# receiver_1.net
KiCad netlist of a schematic drawn in Altium Designer
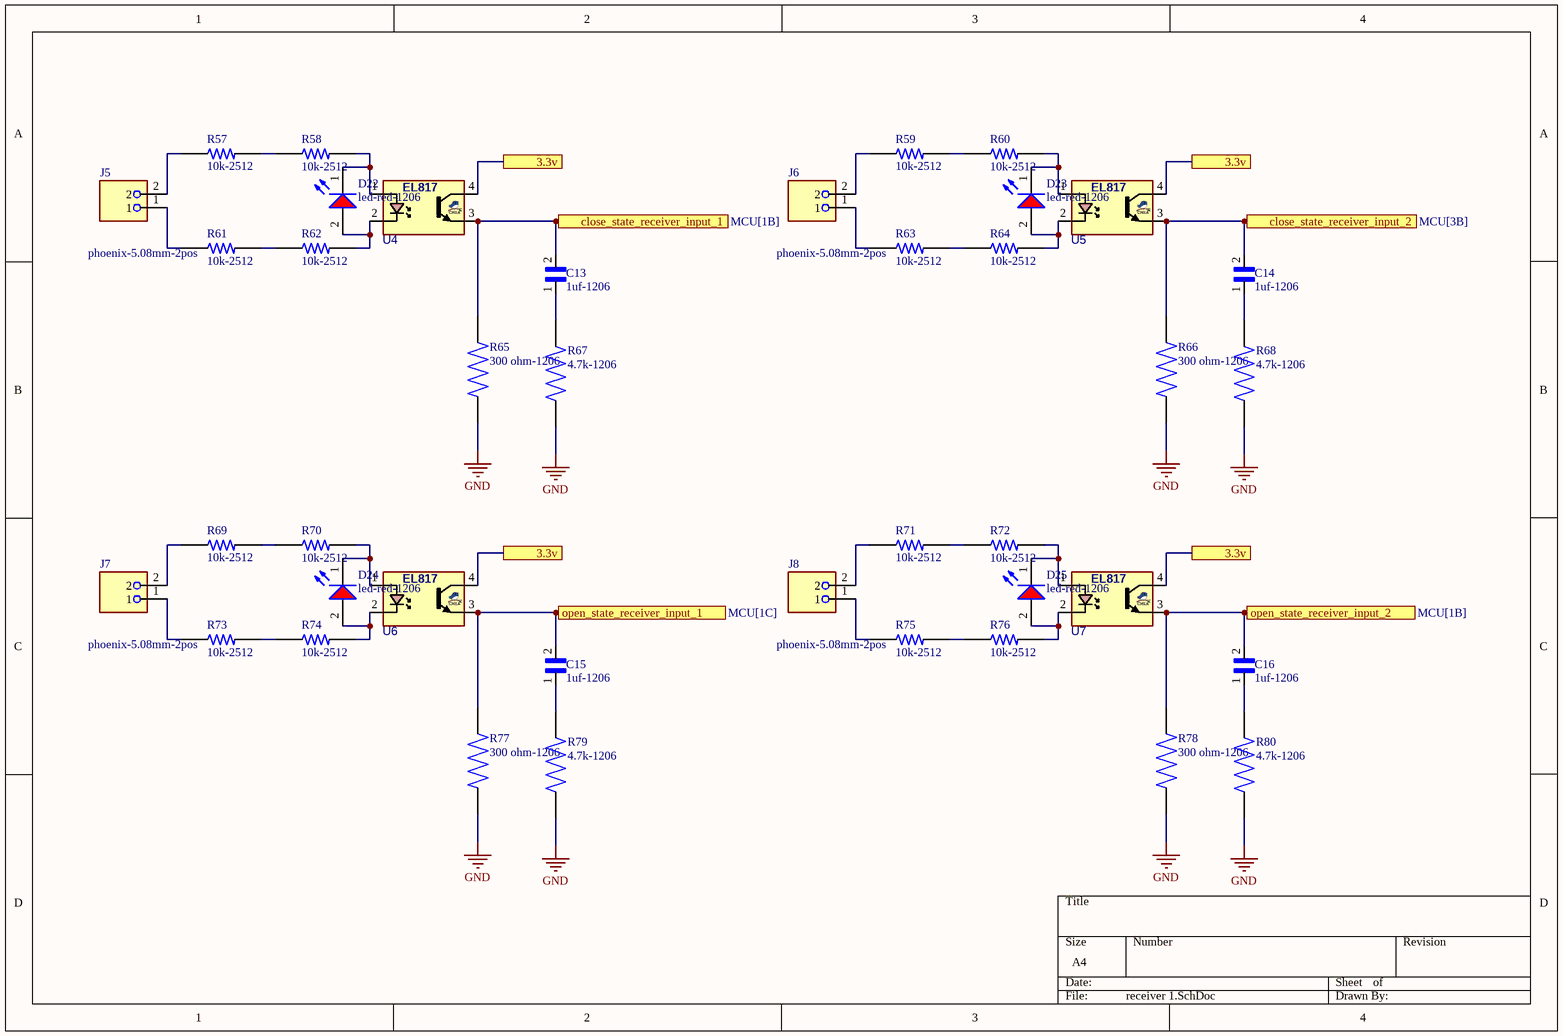
[diagram p0: receiver 1.SchDoc]

(export (version "E")
  (design (tool "Eeschema 10.0.6"))
  (components
    (comp (ref "C13")
      (value "1uf-1206")
      (footprint "CAPC3216X180N")
      (description "1ÂµF Â±20% 50V Ceramic Capacitor X8R 1206 (3216 Metric)")
      (fields (field (name "MF") "TDK") (field (name "MP") "CGA5L3X8R1H105M160AB"))
      (libsource (lib "cap-1206") (part "CGA5L3X8R1H105M160AB"))
    )
    (comp (ref "C14")
      (value "1uf-1206")
      (footprint "CAPC3216X180N")
      (description "1ÂµF Â±20% 50V Ceramic Capacitor X8R 1206 (3216 Metric)")
      (fields (field (name "MF") "TDK") (field (name "MP") "CGA5L3X8R1H105M160AB"))
      (libsource (lib "cap-1206") (part "CGA5L3X8R1H105M160AB"))
    )
    (comp (ref "C15")
      (value "1uf-1206")
      (footprint "CAPC3216X180N")
      (description "1ÂµF Â±20% 50V Ceramic Capacitor X8R 1206 (3216 Metric)")
      (fields (field (name "MF") "TDK") (field (name "MP") "CGA5L3X8R1H105M160AB"))
      (libsource (lib "cap-1206") (part "CGA5L3X8R1H105M160AB"))
    )
    (comp (ref "C16")
      (value "1uf-1206")
      (footprint "CAPC3216X180N")
      (description "1ÂµF Â±20% 50V Ceramic Capacitor X8R 1206 (3216 Metric)")
      (fields (field (name "MF") "TDK") (field (name "MP") "CGA5L3X8R1H105M160AB"))
      (libsource (lib "cap-1206") (part "CGA5L3X8R1H105M160AB"))
    )
    (comp (ref "D22")
      (value "led-red-1206")
      (footprint "WL-SMRW_1206 dome_normal use")
      (description "WL-SMRW Mono-color Reverse mount Waterclear, SMT, size 1206 dome, Red, 2V, 20°")
      (fields
        (field (name "MANUFACTURER PART NUMBER") "156120RS82500")
        (field (name "MANUFACTURER") "Wurth Elektronik")
      )
      (libsource (lib "led-1206") (part "156120RS82500"))
    )
    (comp (ref "D23")
      (value "led-red-1206")
      (footprint "WL-SMRW_1206 dome_normal use")
      (description "WL-SMRW Mono-color Reverse mount Waterclear, SMT, size 1206 dome, Red, 2V, 20°")
      (fields
        (field (name "MANUFACTURER PART NUMBER") "156120RS82500")
        (field (name "MANUFACTURER") "Wurth Elektronik")
      )
      (libsource (lib "led-1206") (part "156120RS82500"))
    )
    (comp (ref "D24")
      (value "led-red-1206")
      (footprint "WL-SMRW_1206 dome_normal use")
      (description "WL-SMRW Mono-color Reverse mount Waterclear, SMT, size 1206 dome, Red, 2V, 20°")
      (fields
        (field (name "MANUFACTURER PART NUMBER") "156120RS82500")
        (field (name "MANUFACTURER") "Wurth Elektronik")
      )
      (libsource (lib "led-1206") (part "156120RS82500"))
    )
    (comp (ref "D25")
      (value "led-red-1206")
      (footprint "WL-SMRW_1206 dome_normal use")
      (description "WL-SMRW Mono-color Reverse mount Waterclear, SMT, size 1206 dome, Red, 2V, 20°")
      (fields
        (field (name "MANUFACTURER PART NUMBER") "156120RS82500")
        (field (name "MANUFACTURER") "Wurth Elektronik")
      )
      (libsource (lib "led-1206") (part "156120RS82500"))
    )
    (comp (ref "J5")
      (value "phoenix-5.08mm-2pos")
      (footprint "PHOENIX_1715721")
      (fields (field (name "MP") "1715721"))
      (libsource (lib "phoenix-2pos") (part "1715721"))
    )
    (comp (ref "J6")
      (value "phoenix-5.08mm-2pos")
      (footprint "PHOENIX_1715721")
      (fields (field (name "MP") "1715721"))
      (libsource (lib "phoenix-2pos") (part "1715721"))
    )
    (comp (ref "J7")
      (value "phoenix-5.08mm-2pos")
      (footprint "PHOENIX_1715721")
      (fields (field (name "MP") "1715721"))
      (libsource (lib "phoenix-2pos") (part "1715721"))
    )
    (comp (ref "J8")
      (value "phoenix-5.08mm-2pos")
      (footprint "PHOENIX_1715721")
      (fields (field (name "MP") "1715721"))
      (libsource (lib "phoenix-2pos") (part "1715721"))
    )
    (comp (ref "R57")
      (value "10k-2512")
      (footprint "RESC6331X70N")
      (description "18 kOhms Â±5% 1.5W Chip Resistor 2512 (6432 Metric) Pulse Withstanding Thick Film")
      (fields (field (name "MF") "TE Connectivity") (field (name "MP") "5-2176246-2"))
      (libsource (lib "resistor-2512") (part "5-2176246-2"))
    )
    (comp (ref "R58")
      (value "10k-2512")
      (footprint "RESC6331X70N")
      (description "18 kOhms Â±5% 1.5W Chip Resistor 2512 (6432 Metric) Pulse Withstanding Thick Film")
      (fields (field (name "MF") "TE Connectivity") (field (name "MP") "5-2176246-2"))
      (libsource (lib "resistor-2512") (part "5-2176246-2"))
    )
    (comp (ref "R59")
      (value "10k-2512")
      (footprint "RESC6331X70N")
      (description "18 kOhms Â±5% 1.5W Chip Resistor 2512 (6432 Metric) Pulse Withstanding Thick Film")
      (fields (field (name "MF") "TE Connectivity") (field (name "MP") "5-2176246-2"))
      (libsource (lib "resistor-2512") (part "5-2176246-2"))
    )
    (comp (ref "R60")
      (value "10k-2512")
      (footprint "RESC6331X70N")
      (description "18 kOhms Â±5% 1.5W Chip Resistor 2512 (6432 Metric) Pulse Withstanding Thick Film")
      (fields (field (name "MF") "TE Connectivity") (field (name "MP") "5-2176246-2"))
      (libsource (lib "resistor-2512") (part "5-2176246-2"))
    )
    (comp (ref "R61")
      (value "10k-2512")
      (footprint "RESC6331X70N")
      (description "18 kOhms Â±5% 1.5W Chip Resistor 2512 (6432 Metric) Pulse Withstanding Thick Film")
      (fields (field (name "MF") "TE Connectivity") (field (name "MP") "5-2176246-2"))
      (libsource (lib "resistor-2512") (part "5-2176246-2"))
    )
    (comp (ref "R62")
      (value "10k-2512")
      (footprint "RESC6331X70N")
      (description "18 kOhms Â±5% 1.5W Chip Resistor 2512 (6432 Metric) Pulse Withstanding Thick Film")
      (fields (field (name "MF") "TE Connectivity") (field (name "MP") "5-2176246-2"))
      (libsource (lib "resistor-2512") (part "5-2176246-2"))
    )
    (comp (ref "R63")
      (value "10k-2512")
      (footprint "RESC6331X70N")
      (description "18 kOhms Â±5% 1.5W Chip Resistor 2512 (6432 Metric) Pulse Withstanding Thick Film")
      (fields (field (name "MF") "TE Connectivity") (field (name "MP") "5-2176246-2"))
      (libsource (lib "resistor-2512") (part "5-2176246-2"))
    )
    (comp (ref "R64")
      (value "10k-2512")
      (footprint "RESC6331X70N")
      (description "18 kOhms Â±5% 1.5W Chip Resistor 2512 (6432 Metric) Pulse Withstanding Thick Film")
      (fields (field (name "MF") "TE Connectivity") (field (name "MP") "5-2176246-2"))
      (libsource (lib "resistor-2512") (part "5-2176246-2"))
    )
    (comp (ref "R65")
      (value "300 ohm-1206")
      (footprint "RESC3015X65N")
      (description "Res Thin Film 1206 10K Ohm 0.1% 1/8W Â±25ppm/Â°C Molded SMD SMD Paper T/R")
      (fields (field (name "MF") "TE Connectivity") (field (name "MP") "CPF1206B10KE1"))
      (libsource (lib "resistor-1206") (part "CPF1206B10KE1"))
    )
    (comp (ref "R66")
      (value "300 ohm-1206")
      (footprint "RESC3015X65N")
      (description "Res Thin Film 1206 10K Ohm 0.1% 1/8W Â±25ppm/Â°C Molded SMD SMD Paper T/R")
      (fields (field (name "MF") "TE Connectivity") (field (name "MP") "CPF1206B10KE1"))
      (libsource (lib "resistor-1206") (part "CPF1206B10KE1"))
    )
    (comp (ref "R67")
      (value "4.7k-1206")
      (footprint "RESC3015X65N")
      (description "Res Thin Film 1206 10K Ohm 0.1% 1/8W Â±25ppm/Â°C Molded SMD SMD Paper T/R")
      (fields (field (name "MF") "TE Connectivity") (field (name "MP") "CPF1206B10KE1"))
      (libsource (lib "resistor-1206") (part "CPF1206B10KE1"))
    )
    (comp (ref "R68")
      (value "4.7k-1206")
      (footprint "RESC3015X65N")
      (description "Res Thin Film 1206 10K Ohm 0.1% 1/8W Â±25ppm/Â°C Molded SMD SMD Paper T/R")
      (fields (field (name "MF") "TE Connectivity") (field (name "MP") "CPF1206B10KE1"))
      (libsource (lib "resistor-1206") (part "CPF1206B10KE1"))
    )
    (comp (ref "R69")
      (value "10k-2512")
      (footprint "RESC6331X70N")
      (description "18 kOhms Â±5% 1.5W Chip Resistor 2512 (6432 Metric) Pulse Withstanding Thick Film")
      (fields (field (name "MF") "TE Connectivity") (field (name "MP") "5-2176246-2"))
      (libsource (lib "resistor-2512") (part "5-2176246-2"))
    )
    (comp (ref "R70")
      (value "10k-2512")
      (footprint "RESC6331X70N")
      (description "18 kOhms Â±5% 1.5W Chip Resistor 2512 (6432 Metric) Pulse Withstanding Thick Film")
      (fields (field (name "MF") "TE Connectivity") (field (name "MP") "5-2176246-2"))
      (libsource (lib "resistor-2512") (part "5-2176246-2"))
    )
    (comp (ref "R71")
      (value "10k-2512")
      (footprint "RESC6331X70N")
      (description "18 kOhms Â±5% 1.5W Chip Resistor 2512 (6432 Metric) Pulse Withstanding Thick Film")
      (fields (field (name "MF") "TE Connectivity") (field (name "MP") "5-2176246-2"))
      (libsource (lib "resistor-2512") (part "5-2176246-2"))
    )
    (comp (ref "R72")
      (value "10k-2512")
      (footprint "RESC6331X70N")
      (description "18 kOhms Â±5% 1.5W Chip Resistor 2512 (6432 Metric) Pulse Withstanding Thick Film")
      (fields (field (name "MF") "TE Connectivity") (field (name "MP") "5-2176246-2"))
      (libsource (lib "resistor-2512") (part "5-2176246-2"))
    )
    (comp (ref "R73")
      (value "10k-2512")
      (footprint "RESC6331X70N")
      (description "18 kOhms Â±5% 1.5W Chip Resistor 2512 (6432 Metric) Pulse Withstanding Thick Film")
      (fields (field (name "MF") "TE Connectivity") (field (name "MP") "5-2176246-2"))
      (libsource (lib "resistor-2512") (part "5-2176246-2"))
    )
    (comp (ref "R74")
      (value "10k-2512")
      (footprint "RESC6331X70N")
      (description "18 kOhms Â±5% 1.5W Chip Resistor 2512 (6432 Metric) Pulse Withstanding Thick Film")
      (fields (field (name "MF") "TE Connectivity") (field (name "MP") "5-2176246-2"))
      (libsource (lib "resistor-2512") (part "5-2176246-2"))
    )
    (comp (ref "R75")
      (value "10k-2512")
      (footprint "RESC6331X70N")
      (description "18 kOhms Â±5% 1.5W Chip Resistor 2512 (6432 Metric) Pulse Withstanding Thick Film")
      (fields (field (name "MF") "TE Connectivity") (field (name "MP") "5-2176246-2"))
      (libsource (lib "resistor-2512") (part "5-2176246-2"))
    )
    (comp (ref "R76")
      (value "10k-2512")
      (footprint "RESC6331X70N")
      (description "18 kOhms Â±5% 1.5W Chip Resistor 2512 (6432 Metric) Pulse Withstanding Thick Film")
      (fields (field (name "MF") "TE Connectivity") (field (name "MP") "5-2176246-2"))
      (libsource (lib "resistor-2512") (part "5-2176246-2"))
    )
    (comp (ref "R77")
      (value "300 ohm-1206")
      (footprint "RESC3015X65N")
      (description "Res Thin Film 1206 10K Ohm 0.1% 1/8W Â±25ppm/Â°C Molded SMD SMD Paper T/R")
      (fields (field (name "MF") "TE Connectivity") (field (name "MP") "CPF1206B10KE1"))
      (libsource (lib "resistor-1206") (part "CPF1206B10KE1"))
    )
    (comp (ref "R78")
      (value "300 ohm-1206")
      (footprint "RESC3015X65N")
      (description "Res Thin Film 1206 10K Ohm 0.1% 1/8W Â±25ppm/Â°C Molded SMD SMD Paper T/R")
      (fields (field (name "MF") "TE Connectivity") (field (name "MP") "CPF1206B10KE1"))
      (libsource (lib "resistor-1206") (part "CPF1206B10KE1"))
    )
    (comp (ref "R79")
      (value "4.7k-1206")
      (footprint "RESC3015X65N")
      (description "Res Thin Film 1206 10K Ohm 0.1% 1/8W Â±25ppm/Â°C Molded SMD SMD Paper T/R")
      (fields (field (name "MF") "TE Connectivity") (field (name "MP") "CPF1206B10KE1"))
      (libsource (lib "resistor-1206") (part "CPF1206B10KE1"))
    )
    (comp (ref "R80")
      (value "4.7k-1206")
      (footprint "RESC3015X65N")
      (description "Res Thin Film 1206 10K Ohm 0.1% 1/8W Â±25ppm/Â°C Molded SMD SMD Paper T/R")
      (fields (field (name "MF") "TE Connectivity") (field (name "MP") "CPF1206B10KE1"))
      (libsource (lib "resistor-1206") (part "CPF1206B10KE1"))
    )
    (comp (ref "U4")
      (value "EL817")
      (footprint "DIP_4SMD")
      (description "OPTOCOUPLER, TRANSISTOR, 4PIN")
      (libsource (lib "optocoupler") (part "OPTC_TR4P_EL817_SMD"))
    )
    (comp (ref "U5")
      (value "EL817")
      (footprint "DIP_4SMD")
      (description "OPTOCOUPLER, TRANSISTOR, 4PIN")
      (libsource (lib "optocoupler") (part "OPTC_TR4P_EL817_SMD"))
    )
    (comp (ref "U6")
      (value "EL817")
      (footprint "DIP_4SMD")
      (description "OPTOCOUPLER, TRANSISTOR, 4PIN")
      (libsource (lib "optocoupler") (part "OPTC_TR4P_EL817_SMD"))
    )
    (comp (ref "U7")
      (value "EL817")
      (footprint "DIP_4SMD")
      (description "OPTOCOUPLER, TRANSISTOR, 4PIN")
      (libsource (lib "optocoupler") (part "OPTC_TR4P_EL817_SMD"))
    )
  )
  (nets
    (net (code "1") (name "/3.3v") (class "Default")
      (node (ref "U4") (pin "4") (pinfunction "C_4") (pintype "passive"))
      (node (ref "U5") (pin "4") (pinfunction "C_4") (pintype "passive"))
      (node (ref "U6") (pin "4") (pinfunction "C_4") (pintype "passive"))
      (node (ref "U7") (pin "4") (pinfunction "C_4") (pintype "passive"))
    )
    (net (code "2") (name "/close_state_receiver_input_1") (class "Default")
      (node (ref "C13") (pin "2") (pinfunction "2_2") (pintype "passive"))
      (node (ref "R65") (pin "2") (pinfunction "2_2") (pintype "passive"))
      (node (ref "U4") (pin "3") (pinfunction "E_3") (pintype "passive"))
    )
    (net (code "3") (name "/close_state_receiver_input_2") (class "Default")
      (node (ref "C14") (pin "2") (pinfunction "2_2") (pintype "passive"))
      (node (ref "R66") (pin "2") (pinfunction "2_2") (pintype "passive"))
      (node (ref "U5") (pin "3") (pinfunction "E_3") (pintype "passive"))
    )
    (net (code "4") (name "/open_state_receiver_input_1") (class "Default")
      (node (ref "C15") (pin "2") (pinfunction "2_2") (pintype "passive"))
      (node (ref "R77") (pin "2") (pinfunction "2_2") (pintype "passive"))
      (node (ref "U6") (pin "3") (pinfunction "E_3") (pintype "passive"))
    )
    (net (code "5") (name "/open_state_receiver_input_2") (class "Default")
      (node (ref "C16") (pin "2") (pinfunction "2_2") (pintype "passive"))
      (node (ref "R78") (pin "2") (pinfunction "2_2") (pintype "passive"))
      (node (ref "U7") (pin "3") (pinfunction "E_3") (pintype "passive"))
    )
    (net (code "6") (name "GND") (class "Default")
      (node (ref "R65") (pin "1") (pinfunction "1_1") (pintype "passive"))
      (node (ref "R66") (pin "1") (pinfunction "1_1") (pintype "passive"))
      (node (ref "R67") (pin "1") (pinfunction "1_1") (pintype "passive"))
      (node (ref "R68") (pin "1") (pinfunction "1_1") (pintype "passive"))
      (node (ref "R77") (pin "1") (pinfunction "1_1") (pintype "passive"))
      (node (ref "R78") (pin "1") (pinfunction "1_1") (pintype "passive"))
      (node (ref "R79") (pin "1") (pinfunction "1_1") (pintype "passive"))
      (node (ref "R80") (pin "1") (pinfunction "1_1") (pintype "passive"))
    )
    (net (code "7") (name "Net-(C13-Pad1)") (class "Default")
      (node (ref "C13") (pin "1") (pinfunction "1_1") (pintype "passive"))
      (node (ref "R67") (pin "2") (pinfunction "2_2") (pintype "passive"))
    )
    (net (code "8") (name "Net-(C14-Pad1)") (class "Default")
      (node (ref "C14") (pin "1") (pinfunction "1_1") (pintype "passive"))
      (node (ref "R68") (pin "2") (pinfunction "2_2") (pintype "passive"))
    )
    (net (code "9") (name "Net-(C15-Pad1)") (class "Default")
      (node (ref "C15") (pin "1") (pinfunction "1_1") (pintype "passive"))
      (node (ref "R79") (pin "2") (pinfunction "2_2") (pintype "passive"))
    )
    (net (code "10") (name "Net-(C16-Pad1)") (class "Default")
      (node (ref "C16") (pin "1") (pinfunction "1_1") (pintype "passive"))
      (node (ref "R80") (pin "2") (pinfunction "2_2") (pintype "passive"))
    )
    (net (code "11") (name "Net-(D22-A)") (class "Default")
      (node (ref "D22") (pin "2") (pinfunction "A_2") (pintype "passive"))
      (node (ref "R62") (pin "2") (pinfunction "2_2") (pintype "passive"))
      (node (ref "U4") (pin "2") (pinfunction "K_2") (pintype "passive"))
    )
    (net (code "12") (name "Net-(D22-K)") (class "Default")
      (node (ref "D22") (pin "1") (pinfunction "K_1") (pintype "passive"))
      (node (ref "R58") (pin "2") (pinfunction "2_2") (pintype "passive"))
      (node (ref "U4") (pin "1") (pinfunction "A_1") (pintype "passive"))
    )
    (net (code "13") (name "Net-(D23-A)") (class "Default")
      (node (ref "D23") (pin "2") (pinfunction "A_2") (pintype "passive"))
      (node (ref "R64") (pin "2") (pinfunction "2_2") (pintype "passive"))
      (node (ref "U5") (pin "2") (pinfunction "K_2") (pintype "passive"))
    )
    (net (code "14") (name "Net-(D23-K)") (class "Default")
      (node (ref "D23") (pin "1") (pinfunction "K_1") (pintype "passive"))
      (node (ref "R60") (pin "2") (pinfunction "2_2") (pintype "passive"))
      (node (ref "U5") (pin "1") (pinfunction "A_1") (pintype "passive"))
    )
    (net (code "15") (name "Net-(D24-A)") (class "Default")
      (node (ref "D24") (pin "2") (pinfunction "A_2") (pintype "passive"))
      (node (ref "R74") (pin "2") (pinfunction "2_2") (pintype "passive"))
      (node (ref "U6") (pin "2") (pinfunction "K_2") (pintype "passive"))
    )
    (net (code "16") (name "Net-(D24-K)") (class "Default")
      (node (ref "D24") (pin "1") (pinfunction "K_1") (pintype "passive"))
      (node (ref "R70") (pin "2") (pinfunction "2_2") (pintype "passive"))
      (node (ref "U6") (pin "1") (pinfunction "A_1") (pintype "passive"))
    )
    (net (code "17") (name "Net-(D25-A)") (class "Default")
      (node (ref "D25") (pin "2") (pinfunction "A_2") (pintype "passive"))
      (node (ref "R76") (pin "2") (pinfunction "2_2") (pintype "passive"))
      (node (ref "U7") (pin "2") (pinfunction "K_2") (pintype "passive"))
    )
    (net (code "18") (name "Net-(D25-K)") (class "Default")
      (node (ref "D25") (pin "1") (pinfunction "K_1") (pintype "passive"))
      (node (ref "R72") (pin "2") (pinfunction "2_2") (pintype "passive"))
      (node (ref "U7") (pin "1") (pinfunction "A_1") (pintype "passive"))
    )
    (net (code "19") (name "Net-(J5-Pad1)") (class "Default")
      (node (ref "J5") (pin "1") (pinfunction "1_1") (pintype "passive"))
      (node (ref "R61") (pin "1") (pinfunction "1_1") (pintype "passive"))
    )
    (net (code "20") (name "Net-(J5-Pad2)") (class "Default")
      (node (ref "J5") (pin "2") (pinfunction "2_2") (pintype "passive"))
      (node (ref "R57") (pin "1") (pinfunction "1_1") (pintype "passive"))
    )
    (net (code "21") (name "Net-(J6-Pad1)") (class "Default")
      (node (ref "J6") (pin "1") (pinfunction "1_1") (pintype "passive"))
      (node (ref "R63") (pin "1") (pinfunction "1_1") (pintype "passive"))
    )
    (net (code "22") (name "Net-(J6-Pad2)") (class "Default")
      (node (ref "J6") (pin "2") (pinfunction "2_2") (pintype "passive"))
      (node (ref "R59") (pin "1") (pinfunction "1_1") (pintype "passive"))
    )
    (net (code "23") (name "Net-(J7-Pad1)") (class "Default")
      (node (ref "J7") (pin "1") (pinfunction "1_1") (pintype "passive"))
      (node (ref "R73") (pin "1") (pinfunction "1_1") (pintype "passive"))
    )
    (net (code "24") (name "Net-(J7-Pad2)") (class "Default")
      (node (ref "J7") (pin "2") (pinfunction "2_2") (pintype "passive"))
      (node (ref "R69") (pin "1") (pinfunction "1_1") (pintype "passive"))
    )
    (net (code "25") (name "Net-(J8-Pad1)") (class "Default")
      (node (ref "J8") (pin "1") (pinfunction "1_1") (pintype "passive"))
      (node (ref "R75") (pin "1") (pinfunction "1_1") (pintype "passive"))
    )
    (net (code "26") (name "Net-(J8-Pad2)") (class "Default")
      (node (ref "J8") (pin "2") (pinfunction "2_2") (pintype "passive"))
      (node (ref "R71") (pin "1") (pinfunction "1_1") (pintype "passive"))
    )
    (net (code "27") (name "Net-(R57-Pad2)") (class "Default")
      (node (ref "R57") (pin "2") (pinfunction "2_2") (pintype "passive"))
      (node (ref "R58") (pin "1") (pinfunction "1_1") (pintype "passive"))
    )
    (net (code "28") (name "Net-(R59-Pad2)") (class "Default")
      (node (ref "R59") (pin "2") (pinfunction "2_2") (pintype "passive"))
      (node (ref "R60") (pin "1") (pinfunction "1_1") (pintype "passive"))
    )
    (net (code "29") (name "Net-(R61-Pad2)") (class "Default")
      (node (ref "R61") (pin "2") (pinfunction "2_2") (pintype "passive"))
      (node (ref "R62") (pin "1") (pinfunction "1_1") (pintype "passive"))
    )
    (net (code "30") (name "Net-(R63-Pad2)") (class "Default")
      (node (ref "R63") (pin "2") (pinfunction "2_2") (pintype "passive"))
      (node (ref "R64") (pin "1") (pinfunction "1_1") (pintype "passive"))
    )
    (net (code "31") (name "Net-(R69-Pad2)") (class "Default")
      (node (ref "R69") (pin "2") (pinfunction "2_2") (pintype "passive"))
      (node (ref "R70") (pin "1") (pinfunction "1_1") (pintype "passive"))
    )
    (net (code "32") (name "Net-(R71-Pad2)") (class "Default")
      (node (ref "R71") (pin "2") (pinfunction "2_2") (pintype "passive"))
      (node (ref "R72") (pin "1") (pinfunction "1_1") (pintype "passive"))
    )
    (net (code "33") (name "Net-(R73-Pad2)") (class "Default")
      (node (ref "R73") (pin "2") (pinfunction "2_2") (pintype "passive"))
      (node (ref "R74") (pin "1") (pinfunction "1_1") (pintype "passive"))
    )
    (net (code "34") (name "Net-(R75-Pad2)") (class "Default")
      (node (ref "R75") (pin "2") (pinfunction "2_2") (pintype "passive"))
      (node (ref "R76") (pin "1") (pinfunction "1_1") (pintype "passive"))
    )
  )
)
